# IN-16_Display.net
KiCad netlist of a schematic drawn in EAGLE
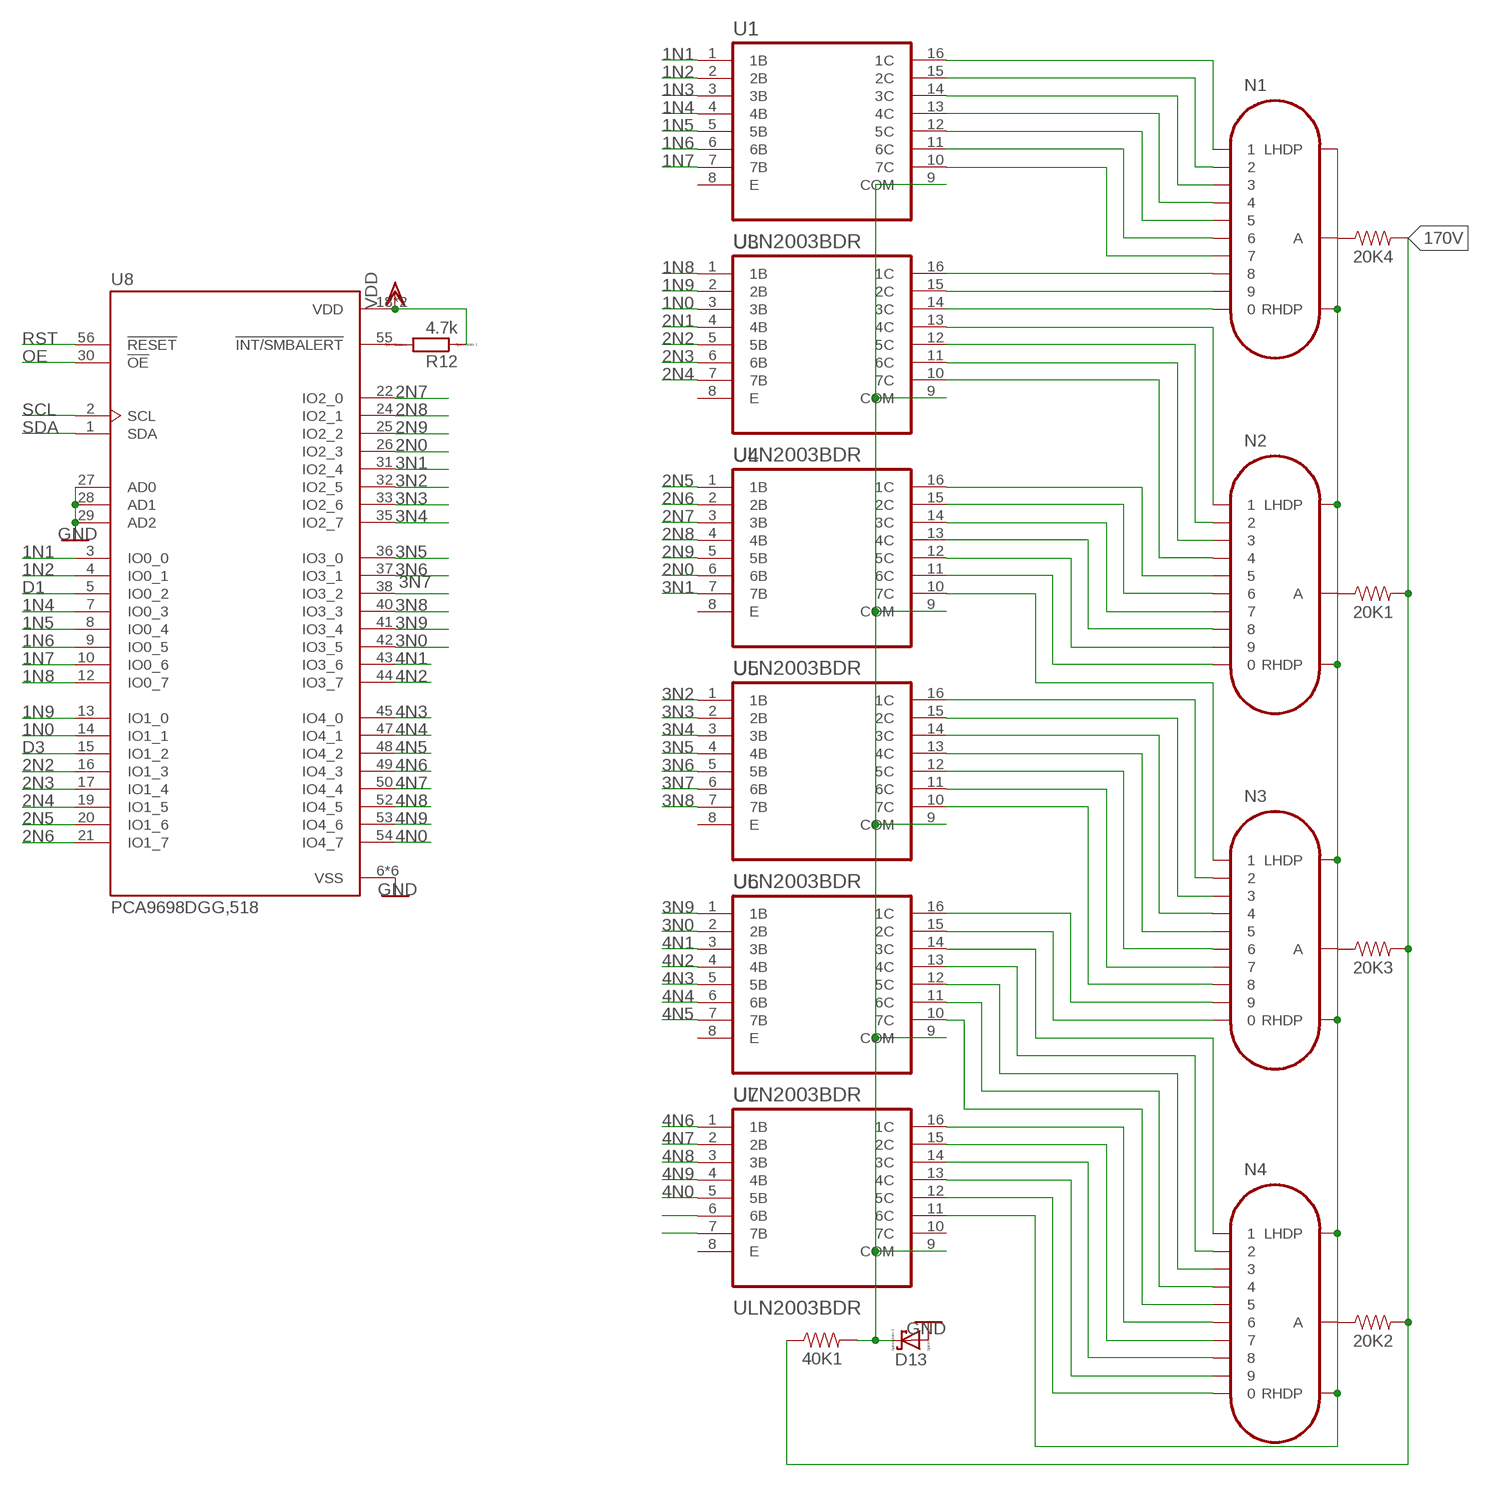
[diagram p0: schematic, sheet 1, part 1 of 2]
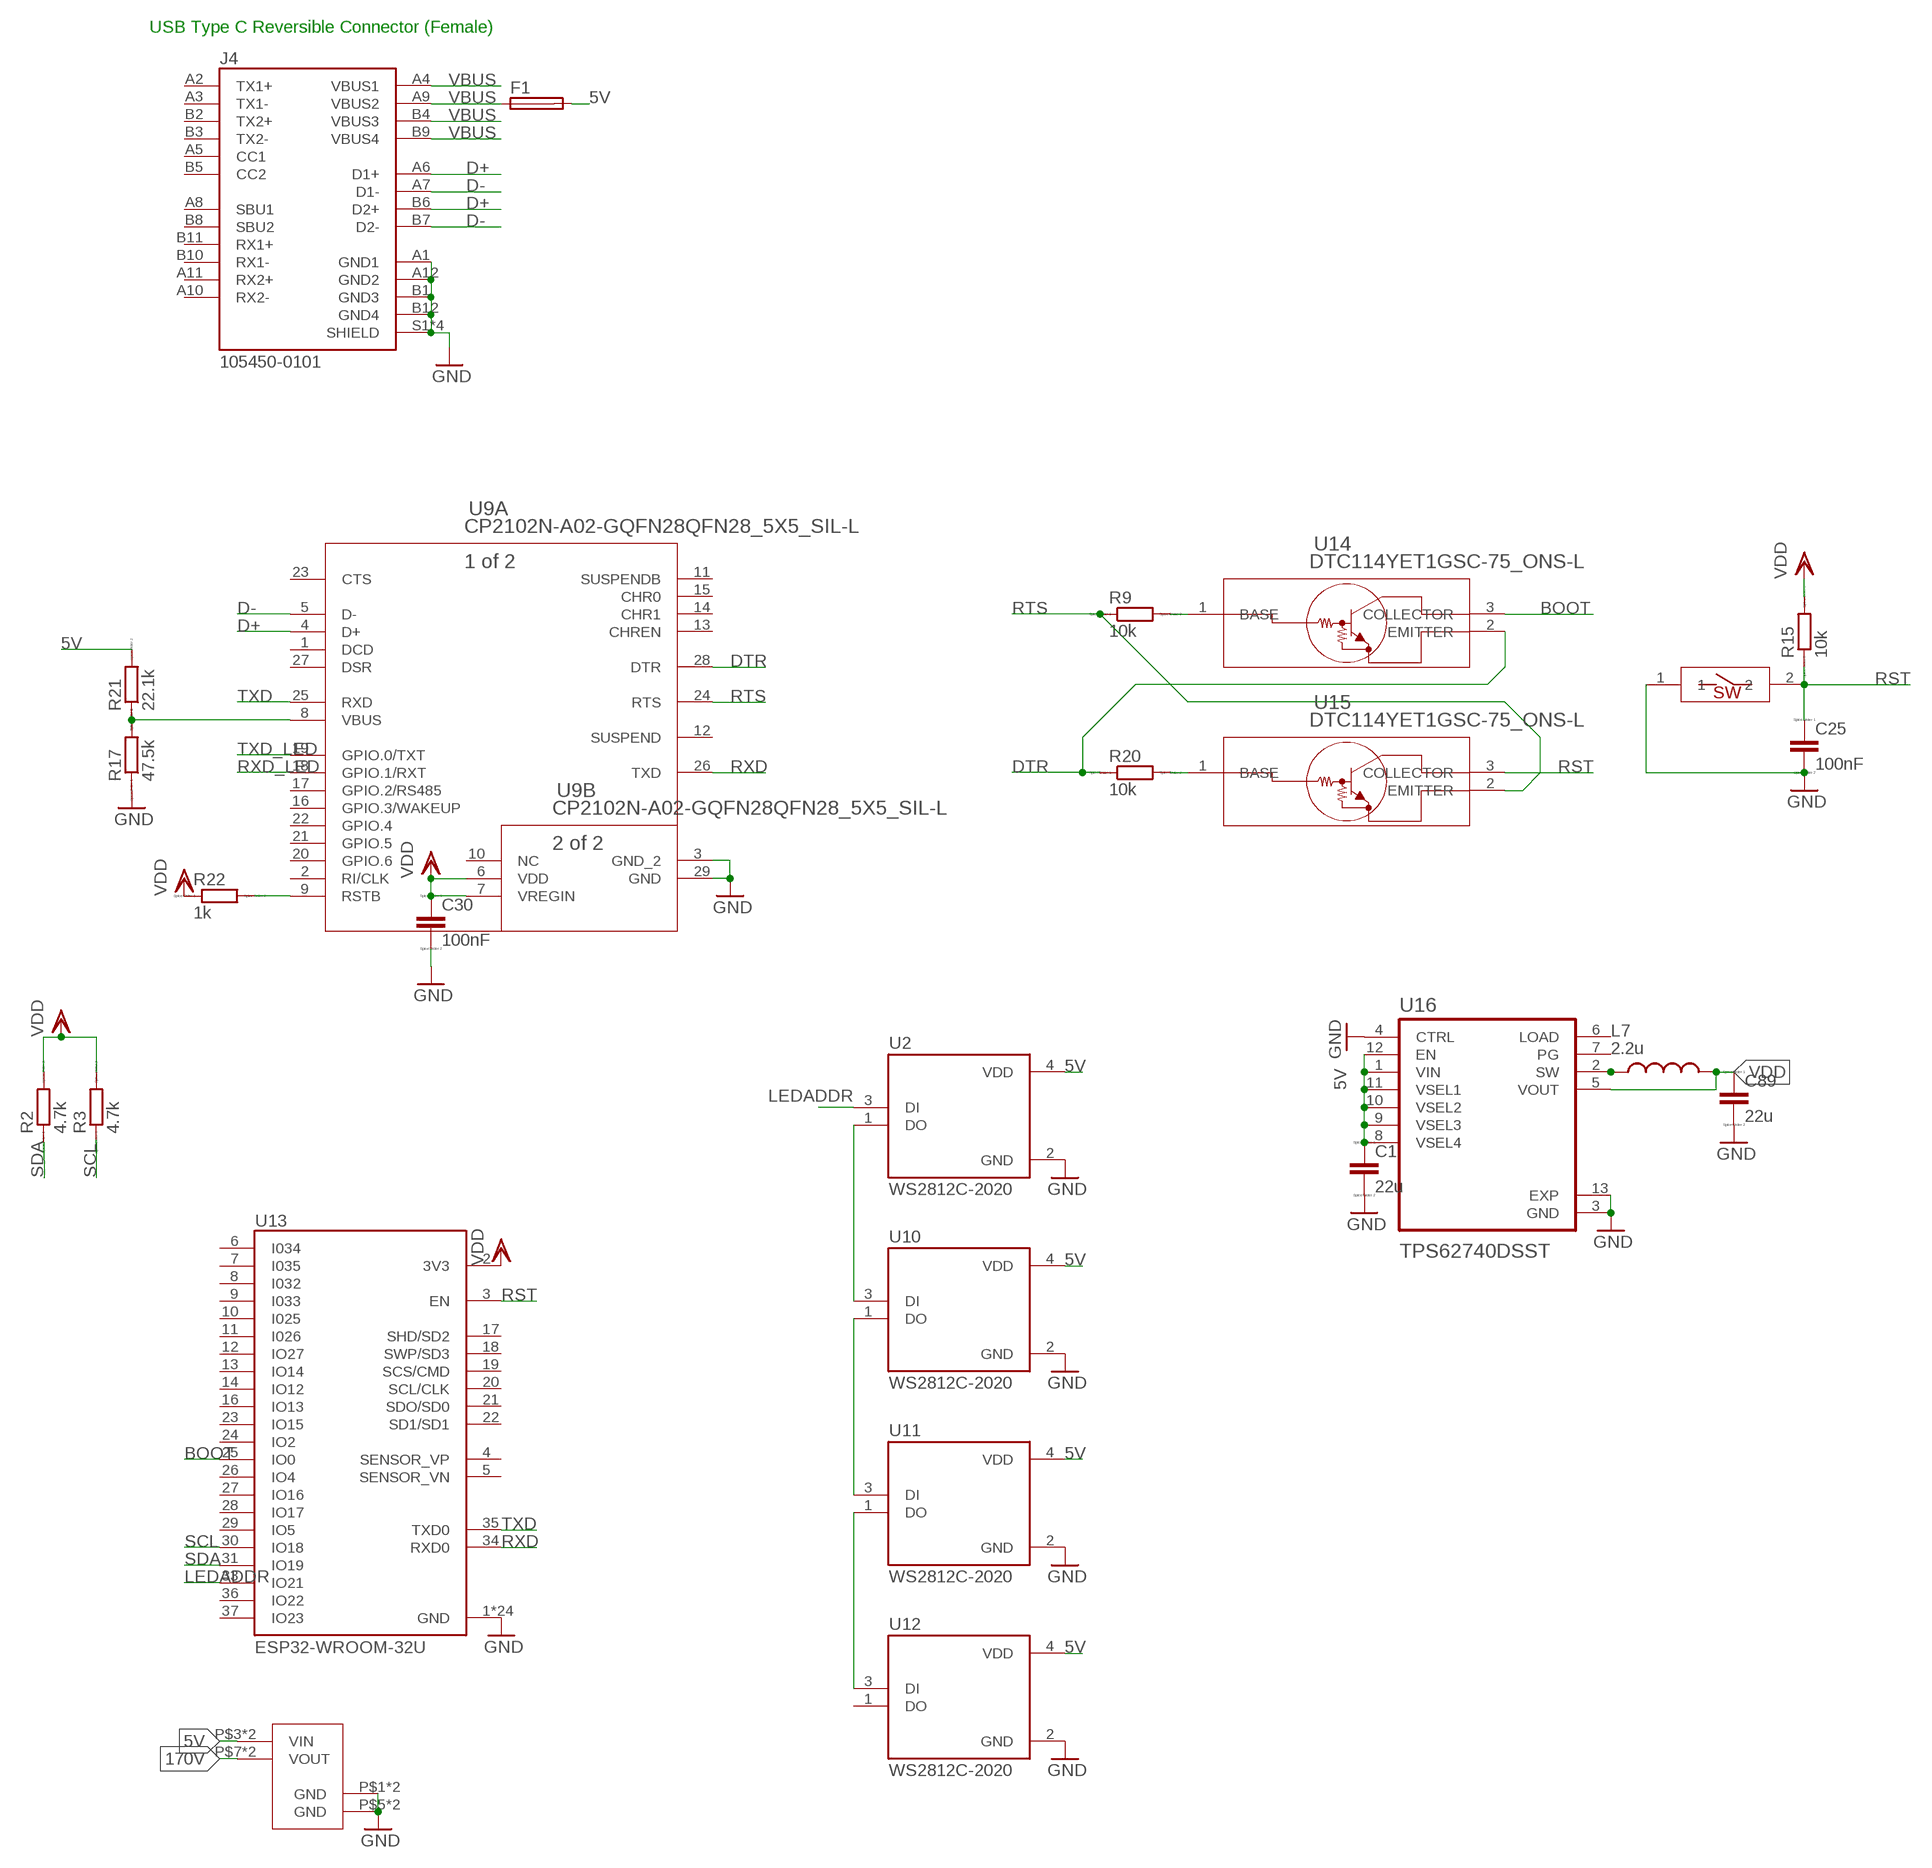
[diagram p1: schematic, sheet 1, part 2 of 2]

(export (version "E")
  (design (tool "Eeschema 10.0.6"))
  (components
    (comp (ref "20K1")
      (value "0.05")
      (footprint "eagle-import:1210")
      (libsource (lib "eagle-import") (part "0.1OHM-1210-1/2W-1%"))
    )
    (comp (ref "20K2")
      (value "0.05")
      (footprint "eagle-import:1210")
      (libsource (lib "eagle-import") (part "0.1OHM-1210-1/2W-1%"))
    )
    (comp (ref "20K3")
      (value "0.05")
      (footprint "eagle-import:1210")
      (libsource (lib "eagle-import") (part "0.1OHM-1210-1/2W-1%"))
    )
    (comp (ref "20K4")
      (value "0.05")
      (footprint "eagle-import:1210")
      (libsource (lib "eagle-import") (part "0.1OHM-1210-1/2W-1%"))
    )
    (comp (ref "40K1")
      (value "0.05")
      (footprint "eagle-import:1210")
      (libsource (lib "eagle-import") (part "0.1OHM-1210-1/2W-1%"))
    )
    (comp (ref "C1")
      (value "22u")
      (footprint "eagle-import:C0603R")
      (libsource (lib "eagle-import") (part "CC0603R"))
    )
    (comp (ref "C25")
      (value "100nF")
      (footprint "eagle-import:C0402")
      (libsource (lib "eagle-import") (part "CC0402"))
    )
    (comp (ref "C30")
      (value "100nF")
      (footprint "eagle-import:C0402")
      (libsource (lib "eagle-import") (part "CC0402"))
    )
    (comp (ref "C89")
      (value "22u")
      (footprint "eagle-import:C0603R")
      (libsource (lib "eagle-import") (part "CC0603R"))
    )
    (comp (ref "D13")
      (value "SCHOTTKY-DIODE")
      (footprint "eagle-import:DIODE_SMB")
      (libsource (lib "eagle-import") (part "SCHOTTKY-DIODE"))
    )
    (comp (ref "F1")
      (value "MF-MSMF050-2")
      (footprint "eagle-import:1812")
      (fields
        (field (name "DIGIKEY_PART_NUMBER") "MF-MSMF050-2TR-ND")
        (field (name "MANUFACTURER") "Bourns Inc.")
        (field (name "CREATED_BY") "PCBLayout.com")
      )
      (libsource (lib "eagle-import") (part "MF-MSMF050-2"))
    )
    (comp (ref "J4")
      (value "105450-0101")
      (footprint "eagle-import:MOLEX_105450-0101")
      (fields (field (name "MF") "Molex") (field (name "MP") "1054500101"))
      (libsource (lib "eagle-import") (part "105450-0101"))
    )
    (comp (ref "L7")
      (value "2.2u")
      (footprint "eagle-import:INDC3225X120N")
      (fields (field (name "MF") "Murata") (field (name "MP") "1277AS-H-1R5M=P2"))
      (libsource (lib "eagle-import") (part "1277AS-H-1R5M=P2"))
    )
    (comp (ref "N1")
      (value "IN-16")
      (footprint "eagle-import:IN-16")
      (libsource (lib "eagle-import") (part "IN-16"))
    )
    (comp (ref "N2")
      (value "IN-16")
      (footprint "eagle-import:IN-16")
      (libsource (lib "eagle-import") (part "IN-16"))
    )
    (comp (ref "N3")
      (value "IN-16")
      (footprint "eagle-import:IN-16")
      (libsource (lib "eagle-import") (part "IN-16"))
    )
    (comp (ref "N4")
      (value "IN-16")
      (footprint "eagle-import:IN-16")
      (libsource (lib "eagle-import") (part "IN-16"))
    )
    (comp (ref "R2")
      (value "4.7k")
      (footprint "eagle-import:R0402")
      (libsource (lib "eagle-import") (part "RR0402"))
    )
    (comp (ref "R3")
      (value "4.7k")
      (footprint "eagle-import:R0402")
      (libsource (lib "eagle-import") (part "RR0402"))
    )
    (comp (ref "R9")
      (value "10k")
      (footprint "eagle-import:R0402")
      (libsource (lib "eagle-import") (part "RR0402"))
    )
    (comp (ref "R12")
      (value "4.7k")
      (footprint "eagle-import:R0402")
      (libsource (lib "eagle-import") (part "RR0402"))
    )
    (comp (ref "R15")
      (value "10k")
      (footprint "eagle-import:R0402")
      (libsource (lib "eagle-import") (part "RR0402"))
    )
    (comp (ref "R17")
      (value "47.5k")
      (footprint "eagle-import:R0402")
      (libsource (lib "eagle-import") (part "RR0402"))
    )
    (comp (ref "R20")
      (value "10k")
      (footprint "eagle-import:R0402")
      (libsource (lib "eagle-import") (part "RR0402"))
    )
    (comp (ref "R21")
      (value "22.1k")
      (footprint "eagle-import:R0402")
      (libsource (lib "eagle-import") (part "RR0402"))
    )
    (comp (ref "R22")
      (value "1k")
      (footprint "eagle-import:R0402")
      (libsource (lib "eagle-import") (part "RR0402"))
    )
    (comp (ref "RESET")
      (value "SMDSWITCH")
      (footprint "eagle-import:RESC4217X170")
      (libsource (lib "eagle-import") (part "SMDSWITCH"))
    )
    (comp (ref "U$1")
      (value "HVPSU")
      (footprint "eagle-import:HVPSU")
      (libsource (lib "eagle-import") (part "HVPSU"))
    )
    (comp (ref "U1")
      (value "ULN2003BDR")
      (footprint "eagle-import:SOIC127P600X175-16N")
      (fields (field (name "MF") "Texas Instruments"))
      (libsource (lib "eagle-import") (part "ULN2003BDR"))
    )
    (comp (ref "U2")
      (value "WS2812C-2020")
      (footprint "eagle-import:LED_WS2812C-2020")
      (fields (field (name "MF") "Worldsemi"))
      (libsource (lib "eagle-import") (part "WS2812C-2020"))
    )
    (comp (ref "U3")
      (value "ULN2003BDR")
      (footprint "eagle-import:SOIC127P600X175-16N")
      (fields (field (name "MF") "Texas Instruments"))
      (libsource (lib "eagle-import") (part "ULN2003BDR"))
    )
    (comp (ref "U4")
      (value "ULN2003BDR")
      (footprint "eagle-import:SOIC127P600X175-16N")
      (fields (field (name "MF") "Texas Instruments"))
      (libsource (lib "eagle-import") (part "ULN2003BDR"))
    )
    (comp (ref "U5")
      (value "ULN2003BDR")
      (footprint "eagle-import:SOIC127P600X175-16N")
      (fields (field (name "MF") "Texas Instruments"))
      (libsource (lib "eagle-import") (part "ULN2003BDR"))
    )
    (comp (ref "U6")
      (value "ULN2003BDR")
      (footprint "eagle-import:SOIC127P600X175-16N")
      (fields (field (name "MF") "Texas Instruments"))
      (libsource (lib "eagle-import") (part "ULN2003BDR"))
    )
    (comp (ref "U7")
      (value "ULN2003BDR")
      (footprint "eagle-import:SOIC127P600X175-16N")
      (fields (field (name "MF") "Texas Instruments"))
      (libsource (lib "eagle-import") (part "ULN2003BDR"))
    )
    (comp (ref "U8")
      (value "PCA9698DGG,518")
      (footprint "eagle-import:SOP50P810X120-56N")
      (fields (field (name "MF") "NXP USA"))
      (libsource (lib "eagle-import") (part "PCA9698DGG,518"))
    )
    (comp (ref "U9")
      (value "CP2102N-A02-GQFN28QFN28_5X5_SIL-L")
      (footprint "eagle-import:QFN28_5X5_SIL-L")
      (fields
        (field (name "MANUFACTURER_PART_NUMBER") "CP2102N-A02-GQFN28")
        (field (name "COPYRIGHT") "Copyright (C) 2018 Accelerated Designs. All rights reserved")
      )
      (libsource (lib "eagle-import") (part "CP2102N-A02-GQFN28QFN28_5X5_SIL-L"))
    )
    (comp (ref "U10")
      (value "WS2812C-2020")
      (footprint "eagle-import:LED_WS2812C-2020")
      (fields (field (name "MF") "Worldsemi"))
      (libsource (lib "eagle-import") (part "WS2812C-2020"))
    )
    (comp (ref "U11")
      (value "WS2812C-2020")
      (footprint "eagle-import:LED_WS2812C-2020")
      (fields (field (name "MF") "Worldsemi"))
      (libsource (lib "eagle-import") (part "WS2812C-2020"))
    )
    (comp (ref "U12")
      (value "WS2812C-2020")
      (footprint "eagle-import:LED_WS2812C-2020")
      (fields (field (name "MF") "Worldsemi"))
      (libsource (lib "eagle-import") (part "WS2812C-2020"))
    )
    (comp (ref "U13")
      (value "ESP32-WROOM-32U")
      (footprint "eagle-import:XCVR_ESP32-WROOM-32U")
      (fields (field (name "MF") "Espressif Systems"))
      (libsource (lib "eagle-import") (part "ESP32-WROOM-32U"))
    )
    (comp (ref "U14")
      (value "DTC114YET1GSC-75_ONS-L")
      (footprint "eagle-import:SC-75_ONS-L")
      (fields
        (field (name "MANUFACTURER_PART_NUMBER") "DTC114YET1G")
        (field (name "COPYRIGHT") "Copyright (C) 2018 Accelerated Designs. All rights reserved")
      )
      (libsource (lib "eagle-import") (part "DTC114YET1GSC-75_ONS-L"))
    )
    (comp (ref "U15")
      (value "DTC114YET1GSC-75_ONS-L")
      (footprint "eagle-import:SC-75_ONS-L")
      (fields
        (field (name "MANUFACTURER_PART_NUMBER") "DTC114YET1G")
        (field (name "COPYRIGHT") "Copyright (C) 2018 Accelerated Designs. All rights reserved")
      )
      (libsource (lib "eagle-import") (part "DTC114YET1GSC-75_ONS-L"))
    )
    (comp (ref "U16")
      (value "TPS62740DSST")
      (footprint "eagle-import:VREG_LM27762DSSR")
      (fields (field (name "MF") "Texas Instruments") (field (name "MP") "TPS62740DSS"))
      (libsource (lib "eagle-import") (part "TPS62740DSST"))
    )
  )
  (nets
    (net (code "1") (name "/1N0") (class "Default")
      (node (ref "U3") (pin "3") (pinfunction "3B_3") (pintype "input"))
      (node (ref "U8") (pin "14") (pinfunction "IO1_1_14") (pintype "bidirectional"))
    )
    (net (code "2") (name "/1N1") (class "Default")
      (node (ref "U1") (pin "1") (pinfunction "1B_1") (pintype "input"))
      (node (ref "U8") (pin "3") (pinfunction "IO0_0_3") (pintype "bidirectional"))
    )
    (net (code "3") (name "/1N2") (class "Default")
      (node (ref "U1") (pin "2") (pinfunction "2B_2") (pintype "input"))
      (node (ref "U8") (pin "4") (pinfunction "IO0_1_4") (pintype "bidirectional"))
    )
    (net (code "4") (name "/1N3") (class "Default")
      (node (ref "U1") (pin "3") (pinfunction "3B_3") (pintype "input"))
    )
    (net (code "5") (name "/1N4") (class "Default")
      (node (ref "U1") (pin "4") (pinfunction "4B_4") (pintype "input"))
      (node (ref "U8") (pin "7") (pinfunction "IO0_3_7") (pintype "bidirectional"))
    )
    (net (code "6") (name "/1N5") (class "Default")
      (node (ref "U1") (pin "5") (pinfunction "5B_5") (pintype "input"))
      (node (ref "U8") (pin "8") (pinfunction "IO0_4_8") (pintype "bidirectional"))
    )
    (net (code "7") (name "/1N6") (class "Default")
      (node (ref "U1") (pin "6") (pinfunction "6B_6") (pintype "input"))
      (node (ref "U8") (pin "9") (pinfunction "IO0_5_9") (pintype "bidirectional"))
    )
    (net (code "8") (name "/1N7") (class "Default")
      (node (ref "U1") (pin "7") (pinfunction "7B_7") (pintype "input"))
      (node (ref "U8") (pin "10") (pinfunction "IO0_6_10") (pintype "bidirectional"))
    )
    (net (code "9") (name "/1N8") (class "Default")
      (node (ref "U3") (pin "1") (pinfunction "1B_1") (pintype "input"))
      (node (ref "U8") (pin "12") (pinfunction "IO0_7_12") (pintype "bidirectional"))
    )
    (net (code "10") (name "/1N9") (class "Default")
      (node (ref "U3") (pin "2") (pinfunction "2B_2") (pintype "input"))
      (node (ref "U8") (pin "13") (pinfunction "IO1_0_13") (pintype "bidirectional"))
    )
    (net (code "11") (name "/2N0") (class "Default")
      (node (ref "U4") (pin "6") (pinfunction "6B_6") (pintype "input"))
      (node (ref "U8") (pin "26") (pinfunction "IO2_3_26") (pintype "bidirectional"))
    )
    (net (code "12") (name "/2N1") (class "Default")
      (node (ref "U3") (pin "4") (pinfunction "4B_4") (pintype "input"))
    )
    (net (code "13") (name "/2N2") (class "Default")
      (node (ref "U3") (pin "5") (pinfunction "5B_5") (pintype "input"))
      (node (ref "U8") (pin "16") (pinfunction "IO1_3_16") (pintype "bidirectional"))
    )
    (net (code "14") (name "/2N3") (class "Default")
      (node (ref "U3") (pin "6") (pinfunction "6B_6") (pintype "input"))
      (node (ref "U8") (pin "17") (pinfunction "IO1_4_17") (pintype "bidirectional"))
    )
    (net (code "15") (name "/2N4") (class "Default")
      (node (ref "U3") (pin "7") (pinfunction "7B_7") (pintype "input"))
      (node (ref "U8") (pin "19") (pinfunction "IO1_5_19") (pintype "bidirectional"))
    )
    (net (code "16") (name "/2N5") (class "Default")
      (node (ref "U4") (pin "1") (pinfunction "1B_1") (pintype "input"))
      (node (ref "U8") (pin "20") (pinfunction "IO1_6_20") (pintype "bidirectional"))
    )
    (net (code "17") (name "/2N6") (class "Default")
      (node (ref "U4") (pin "2") (pinfunction "2B_2") (pintype "input"))
      (node (ref "U8") (pin "21") (pinfunction "IO1_7_21") (pintype "bidirectional"))
    )
    (net (code "18") (name "/2N7") (class "Default")
      (node (ref "U4") (pin "3") (pinfunction "3B_3") (pintype "input"))
      (node (ref "U8") (pin "22") (pinfunction "IO2_0_22") (pintype "bidirectional"))
    )
    (net (code "19") (name "/2N8") (class "Default")
      (node (ref "U4") (pin "4") (pinfunction "4B_4") (pintype "input"))
      (node (ref "U8") (pin "24") (pinfunction "IO2_1_24") (pintype "bidirectional"))
    )
    (net (code "20") (name "/2N9") (class "Default")
      (node (ref "U4") (pin "5") (pinfunction "5B_5") (pintype "input"))
      (node (ref "U8") (pin "25") (pinfunction "IO2_2_25") (pintype "bidirectional"))
    )
    (net (code "21") (name "/3N0") (class "Default")
      (node (ref "U6") (pin "2") (pinfunction "2B_2") (pintype "input"))
      (node (ref "U8") (pin "42") (pinfunction "IO3_5_42") (pintype "bidirectional"))
    )
    (net (code "22") (name "/3N1") (class "Default")
      (node (ref "U4") (pin "7") (pinfunction "7B_7") (pintype "input"))
      (node (ref "U8") (pin "31") (pinfunction "IO2_4_31") (pintype "bidirectional"))
    )
    (net (code "23") (name "/3N2") (class "Default")
      (node (ref "U5") (pin "1") (pinfunction "1B_1") (pintype "input"))
      (node (ref "U8") (pin "32") (pinfunction "IO2_5_32") (pintype "bidirectional"))
    )
    (net (code "24") (name "/3N3") (class "Default")
      (node (ref "U5") (pin "2") (pinfunction "2B_2") (pintype "input"))
      (node (ref "U8") (pin "33") (pinfunction "IO2_6_33") (pintype "bidirectional"))
    )
    (net (code "25") (name "/3N4") (class "Default")
      (node (ref "U5") (pin "3") (pinfunction "3B_3") (pintype "input"))
      (node (ref "U8") (pin "35") (pinfunction "IO2_7_35") (pintype "bidirectional"))
    )
    (net (code "26") (name "/3N5") (class "Default")
      (node (ref "U5") (pin "4") (pinfunction "4B_4") (pintype "input"))
      (node (ref "U8") (pin "36") (pinfunction "IO3_0_36") (pintype "bidirectional"))
    )
    (net (code "27") (name "/3N6") (class "Default")
      (node (ref "U5") (pin "5") (pinfunction "5B_5") (pintype "input"))
      (node (ref "U8") (pin "37") (pinfunction "IO3_1_37") (pintype "bidirectional"))
    )
    (net (code "28") (name "/3N7") (class "Default")
      (node (ref "U5") (pin "6") (pinfunction "6B_6") (pintype "input"))
      (node (ref "U8") (pin "38") (pinfunction "IO3_2_38") (pintype "bidirectional"))
    )
    (net (code "29") (name "/3N8") (class "Default")
      (node (ref "U5") (pin "7") (pinfunction "7B_7") (pintype "input"))
      (node (ref "U8") (pin "40") (pinfunction "IO3_3_40") (pintype "bidirectional"))
    )
    (net (code "30") (name "/3N9") (class "Default")
      (node (ref "U6") (pin "1") (pinfunction "1B_1") (pintype "input"))
      (node (ref "U8") (pin "41") (pinfunction "IO3_4_41") (pintype "bidirectional"))
    )
    (net (code "31") (name "/4N0") (class "Default")
      (node (ref "U7") (pin "5") (pinfunction "5B_5") (pintype "input"))
      (node (ref "U8") (pin "54") (pinfunction "IO4_7_54") (pintype "bidirectional"))
    )
    (net (code "32") (name "/4N1") (class "Default")
      (node (ref "U6") (pin "3") (pinfunction "3B_3") (pintype "input"))
      (node (ref "U8") (pin "43") (pinfunction "IO3_6_43") (pintype "bidirectional"))
    )
    (net (code "33") (name "/4N2") (class "Default")
      (node (ref "U6") (pin "4") (pinfunction "4B_4") (pintype "input"))
      (node (ref "U8") (pin "44") (pinfunction "IO3_7_44") (pintype "bidirectional"))
    )
    (net (code "34") (name "/4N3") (class "Default")
      (node (ref "U6") (pin "5") (pinfunction "5B_5") (pintype "input"))
      (node (ref "U8") (pin "45") (pinfunction "IO4_0_45") (pintype "bidirectional"))
    )
    (net (code "35") (name "/4N4") (class "Default")
      (node (ref "U6") (pin "6") (pinfunction "6B_6") (pintype "input"))
      (node (ref "U8") (pin "47") (pinfunction "IO4_1_47") (pintype "bidirectional"))
    )
    (net (code "36") (name "/4N5") (class "Default")
      (node (ref "U6") (pin "7") (pinfunction "7B_7") (pintype "input"))
      (node (ref "U8") (pin "48") (pinfunction "IO4_2_48") (pintype "bidirectional"))
    )
    (net (code "37") (name "/4N6") (class "Default")
      (node (ref "U7") (pin "1") (pinfunction "1B_1") (pintype "input"))
      (node (ref "U8") (pin "49") (pinfunction "IO4_3_49") (pintype "bidirectional"))
    )
    (net (code "38") (name "/4N7") (class "Default")
      (node (ref "U7") (pin "2") (pinfunction "2B_2") (pintype "input"))
      (node (ref "U8") (pin "50") (pinfunction "IO4_4_50") (pintype "bidirectional"))
    )
    (net (code "39") (name "/4N8") (class "Default")
      (node (ref "U7") (pin "3") (pinfunction "3B_3") (pintype "input"))
      (node (ref "U8") (pin "52") (pinfunction "IO4_5_52") (pintype "bidirectional"))
    )
    (net (code "40") (name "/4N9") (class "Default")
      (node (ref "U7") (pin "4") (pinfunction "4B_4") (pintype "input"))
      (node (ref "U8") (pin "53") (pinfunction "IO4_6_53") (pintype "bidirectional"))
    )
    (net (code "41") (name "/BOOT") (class "Default")
      (node (ref "U13") (pin "25") (pinfunction "IO0_25") (pintype "bidirectional"))
      (node (ref "U14") (pin "3") (pinfunction "COLLECTOR_3") (pintype "output"))
    )
    (net (code "42") (name "/D+") (class "Default")
      (node (ref "J4") (pin "A6") (pinfunction "D1+_A6") (pintype "passive"))
      (node (ref "J4") (pin "B6") (pinfunction "D2+_B6") (pintype "passive"))
      (node (ref "U9") (pin "4") (pinfunction "D+_4") (pintype "input"))
    )
    (net (code "43") (name "/D-") (class "Default")
      (node (ref "J4") (pin "A7") (pinfunction "D1-_A7") (pintype "passive"))
      (node (ref "J4") (pin "B7") (pinfunction "D2-_B7") (pintype "passive"))
      (node (ref "U9") (pin "5") (pinfunction "D-_5") (pintype "input"))
    )
    (net (code "44") (name "/D1") (class "Default")
      (node (ref "U8") (pin "5") (pinfunction "IO0_2_5") (pintype "bidirectional"))
    )
    (net (code "45") (name "/D3") (class "Default")
      (node (ref "U8") (pin "15") (pinfunction "IO1_2_15") (pintype "bidirectional"))
    )
    (net (code "46") (name "/DTR") (class "Default")
      (node (ref "R20") (pin "1") (pinfunction "1_1") (pintype "passive"))
      (node (ref "U14") (pin "2") (pinfunction "EMITTER_2") (pintype "passive"))
      (node (ref "U9") (pin "28") (pinfunction "DTR_28") (pintype "output"))
    )
    (net (code "47") (name "/LEDADDR") (class "Default")
      (node (ref "U13") (pin "33") (pinfunction "IO21_33") (pintype "bidirectional"))
      (node (ref "U2") (pin "3") (pinfunction "DI_3") (pintype "input"))
    )
    (net (code "48") (name "/OE") (class "Default")
      (node (ref "U8") (pin "30") (pinfunction "~{OE}_30") (pintype "input"))
    )
    (net (code "49") (name "/RST") (class "Default")
      (node (ref "C25") (pin "1") (pinfunction "1_1") (pintype "passive"))
      (node (ref "R15") (pin "1") (pinfunction "1_1") (pintype "passive"))
      (node (ref "RESET") (pin "2") (pinfunction "2_2") (pintype "bidirectional"))
      (node (ref "U13") (pin "3") (pinfunction "EN_3") (pintype "input"))
      (node (ref "U15") (pin "3") (pinfunction "COLLECTOR_3") (pintype "output"))
      (node (ref "U8") (pin "56") (pinfunction "~{RESET}_56") (pintype "input"))
    )
    (net (code "50") (name "/RTS") (class "Default")
      (node (ref "R9") (pin "1") (pinfunction "1_1") (pintype "passive"))
      (node (ref "U15") (pin "2") (pinfunction "EMITTER_2") (pintype "passive"))
      (node (ref "U9") (pin "24") (pinfunction "RTS_24") (pintype "output"))
    )
    (net (code "51") (name "/RXD") (class "Default")
      (node (ref "U13") (pin "34") (pinfunction "RXD0_34") (pintype "bidirectional"))
      (node (ref "U9") (pin "26") (pinfunction "TXD_26") (pintype "output"))
    )
    (net (code "52") (name "/RXD_LED") (class "Default")
      (node (ref "U9") (pin "18") (pinfunction "GPIO.1/RXT_18") (pintype "bidirectional"))
    )
    (net (code "53") (name "/SCL") (class "Default")
      (node (ref "R3") (pin "1") (pinfunction "1_1") (pintype "passive"))
      (node (ref "U13") (pin "30") (pinfunction "IO18_30") (pintype "bidirectional"))
      (node (ref "U8") (pin "2") (pinfunction "SCL_2") (pintype "input"))
    )
    (net (code "54") (name "/SDA") (class "Default")
      (node (ref "R2") (pin "1") (pinfunction "1_1") (pintype "passive"))
      (node (ref "U13") (pin "31") (pinfunction "IO19_31") (pintype "bidirectional"))
      (node (ref "U8") (pin "1") (pinfunction "SDA_1") (pintype "bidirectional"))
    )
    (net (code "55") (name "/TXD") (class "Default")
      (node (ref "U13") (pin "35") (pinfunction "TXD0_35") (pintype "bidirectional"))
      (node (ref "U9") (pin "25") (pinfunction "RXD_25") (pintype "input"))
    )
    (net (code "56") (name "/TXD_LED") (class "Default")
      (node (ref "U9") (pin "19") (pinfunction "GPIO.0/TXT_19") (pintype "bidirectional"))
    )
    (net (code "57") (name "/VBUS") (class "Default")
      (node (ref "F1") (pin "1") (pinfunction "1_1") (pintype "passive"))
      (node (ref "J4") (pin "A4") (pinfunction "VBUS1_A4") (pintype "passive"))
      (node (ref "J4") (pin "A9") (pinfunction "VBUS2_A9") (pintype "passive"))
      (node (ref "J4") (pin "B4") (pinfunction "VBUS3_B4") (pintype "passive"))
      (node (ref "J4") (pin "B9") (pinfunction "VBUS4_B9") (pintype "passive"))
    )
    (net (code "58") (name "5V") (class "Default")
      (node (ref "C1") (pin "1") (pinfunction "1_1") (pintype "passive"))
      (node (ref "F1") (pin "2") (pinfunction "2_2") (pintype "passive"))
      (node (ref "R21") (pin "2") (pinfunction "2_2") (pintype "passive"))
      (node (ref "U$1") (pin "P$3") (pinfunction "VIN_P$3") (pintype "bidirectional"))
      (node (ref "U$1") (pin "P$4") (pinfunction "VIN_P$4") (pintype "bidirectional"))
      (node (ref "U10") (pin "4") (pinfunction "VDD_4") (pintype "power_in"))
      (node (ref "U11") (pin "4") (pinfunction "VDD_4") (pintype "power_in"))
      (node (ref "U12") (pin "4") (pinfunction "VDD_4") (pintype "power_in"))
      (node (ref "U16") (pin "1") (pinfunction "VIN_1") (pintype "input"))
      (node (ref "U16") (pin "10") (pinfunction "VSEL2_10") (pintype "input"))
      (node (ref "U16") (pin "11") (pinfunction "VSEL1_11") (pintype "input"))
      (node (ref "U16") (pin "12") (pinfunction "EN_12") (pintype "input"))
      (node (ref "U16") (pin "8") (pinfunction "VSEL4_8") (pintype "input"))
      (node (ref "U16") (pin "9") (pinfunction "VSEL3_9") (pintype "input"))
      (node (ref "U2") (pin "4") (pinfunction "VDD_4") (pintype "power_in"))
    )
    (net (code "59") (name "170V") (class "Default")
      (node (ref "20K1") (pin "2") (pinfunction "2_2") (pintype "passive"))
      (node (ref "20K2") (pin "2") (pinfunction "2_2") (pintype "passive"))
      (node (ref "20K3") (pin "2") (pinfunction "2_2") (pintype "passive"))
      (node (ref "20K4") (pin "2") (pinfunction "2_2") (pintype "passive"))
      (node (ref "40K1") (pin "1") (pinfunction "1_1") (pintype "passive"))
      (node (ref "U$1") (pin "P$7") (pinfunction "VOUT_P$7") (pintype "bidirectional"))
      (node (ref "U$1") (pin "P$8") (pinfunction "VOUT_P$8") (pintype "bidirectional"))
    )
    (net (code "60") (name "GND") (class "Default")
      (node (ref "C1") (pin "2") (pinfunction "2_2") (pintype "passive"))
      (node (ref "C25") (pin "2") (pinfunction "2_2") (pintype "passive"))
      (node (ref "C30") (pin "2") (pinfunction "2_2") (pintype "passive"))
      (node (ref "C89") (pin "2") (pinfunction "2_2") (pintype "passive"))
      (node (ref "D13") (pin "A") (pinfunction "C_A") (pintype "passive"))
      (node (ref "J4") (pin "A1") (pinfunction "GND1_A1") (pintype "passive"))
      (node (ref "J4") (pin "A12") (pinfunction "GND2_A12") (pintype "passive"))
      (node (ref "J4") (pin "B1") (pinfunction "GND3_B1") (pintype "passive"))
      (node (ref "J4") (pin "B12") (pinfunction "GND4_B12") (pintype "passive"))
      (node (ref "J4") (pin "S1") (pinfunction "SHIELD_S1") (pintype "passive"))
      (node (ref "J4") (pin "S2") (pinfunction "SHIELD_S2") (pintype "passive"))
      (node (ref "J4") (pin "S3") (pinfunction "SHIELD_S3") (pintype "passive"))
      (node (ref "J4") (pin "S4") (pinfunction "SHIELD_S4") (pintype "passive"))
      (node (ref "R17") (pin "1") (pinfunction "1_1") (pintype "passive"))
      (node (ref "RESET") (pin "1") (pinfunction "1_1") (pintype "bidirectional"))
      (node (ref "U$1") (pin "P$1") (pinfunction "GND_P$1") (pintype "bidirectional"))
      (node (ref "U$1") (pin "P$2") (pinfunction "GND_P$2") (pintype "bidirectional"))
      (node (ref "U$1") (pin "P$5") (pinfunction "GND_P$5") (pintype "bidirectional"))
      (node (ref "U$1") (pin "P$6") (pinfunction "GND_P$6") (pintype "bidirectional"))
      (node (ref "U10") (pin "2") (pinfunction "GND_2") (pintype "power_in"))
      (node (ref "U11") (pin "2") (pinfunction "GND_2") (pintype "power_in"))
      (node (ref "U12") (pin "2") (pinfunction "GND_2") (pintype "power_in"))
      (node (ref "U13") (pin "1") (pinfunction "GND_1") (pintype "power_in"))
      (node (ref "U13") (pin "15") (pinfunction "GND_15") (pintype "power_in"))
      (node (ref "U13") (pin "38") (pinfunction "GND_38") (pintype "power_in"))
      (node (ref "U13") (pin "G.1") (pinfunction "GND_G.1") (pintype "power_in"))
      (node (ref "U13") (pin "G.10") (pinfunction "GND_G.10") (pintype "power_in"))
      (node (ref "U13") (pin "G.11") (pinfunction "GND_G.11") (pintype "power_in"))
      (node (ref "U13") (pin "G.12") (pinfunction "GND_G.12") (pintype "power_in"))
      (node (ref "U13") (pin "G.13") (pinfunction "GND_G.13") (pintype "power_in"))
      (node (ref "U13") (pin "G.14") (pinfunction "GND_G.14") (pintype "power_in"))
      (node (ref "U13") (pin "G.15") (pinfunction "GND_G.15") (pintype "power_in"))
      (node (ref "U13") (pin "G.16") (pinfunction "GND_G.16") (pintype "power_in"))
      (node (ref "U13") (pin "G.17") (pinfunction "GND_G.17") (pintype "power_in"))
      (node (ref "U13") (pin "G.18") (pinfunction "GND_G.18") (pintype "power_in"))
      (node (ref "U13") (pin "G.19") (pinfunction "GND_G.19") (pintype "power_in"))
      (node (ref "U13") (pin "G.2") (pinfunction "GND_G.2") (pintype "power_in"))
      (node (ref "U13") (pin "G.20") (pinfunction "GND_G.20") (pintype "power_in"))
      (node (ref "U13") (pin "G.21") (pinfunction "GND_G.21") (pintype "power_in"))
      (node (ref "U13") (pin "G.22") (pinfunction "GND_G.22") (pintype "power_in"))
      (node (ref "U13") (pin "G.4") (pinfunction "GND_G.4") (pintype "power_in"))
      (node (ref "U13") (pin "G.5") (pinfunction "GND_G.5") (pintype "power_in"))
      (node (ref "U13") (pin "G.6") (pinfunction "GND_G.6") (pintype "power_in"))
      (node (ref "U13") (pin "G.7") (pinfunction "GND_G.7") (pintype "power_in"))
      (node (ref "U13") (pin "G.8") (pinfunction "GND_G.8") (pintype "power_in"))
      (node (ref "U13") (pin "G.9") (pinfunction "GND_G.9") (pintype "power_in"))
      (node (ref "U16") (pin "13") (pinfunction "EXP_13") (pintype "power_in"))
      (node (ref "U16") (pin "3") (pinfunction "GND_3") (pintype "power_in"))
      (node (ref "U16") (pin "4") (pinfunction "CTRL_4") (pintype "input"))
      (node (ref "U2") (pin "2") (pinfunction "GND_2") (pintype "power_in"))
      (node (ref "U8") (pin "11") (pinfunction "VSS_11") (pintype "power_in"))
      (node (ref "U8") (pin "23") (pinfunction "VSS_23") (pintype "power_in"))
      (node (ref "U8") (pin "27") (pinfunction "AD0_27") (pintype "input"))
      (node (ref "U8") (pin "28") (pinfunction "AD1_28") (pintype "input"))
      (node (ref "U8") (pin "29") (pinfunction "AD2_29") (pintype "input"))
      (node (ref "U8") (pin "34") (pinfunction "VSS_34") (pintype "power_in"))
      (node (ref "U8") (pin "39") (pinfunction "VSS_39") (pintype "power_in"))
      (node (ref "U8") (pin "51") (pinfunction "VSS_51") (pintype "power_in"))
      (node (ref "U8") (pin "6") (pinfunction "VSS_6") (pintype "power_in"))
      (node (ref "U9") (pin "29") (pinfunction "GND_29") (pintype "passive"))
      (node (ref "U9") (pin "3") (pinfunction "GND_2_3") (pintype "passive"))
    )
    (net (code "61") (name "Net-(20K1-Pad1)") (class "Default")
      (node (ref "20K1") (pin "1") (pinfunction "1_1") (pintype "passive"))
      (node (ref "N2") (pin "A") (pinfunction "A_A") (pintype "bidirectional"))
    )
    (net (code "62") (name "Net-(20K2-Pad1)") (class "Default")
      (node (ref "20K2") (pin "1") (pinfunction "1_1") (pintype "passive"))
      (node (ref "N4") (pin "A") (pinfunction "A_A") (pintype "bidirectional"))
    )
    (net (code "63") (name "Net-(20K3-Pad1)") (class "Default")
      (node (ref "20K3") (pin "1") (pinfunction "1_1") (pintype "passive"))
      (node (ref "N3") (pin "A") (pinfunction "A_A") (pintype "bidirectional"))
    )
    (net (code "64") (name "Net-(20K4-Pad1)") (class "Default")
      (node (ref "20K4") (pin "1") (pinfunction "1_1") (pintype "passive"))
      (node (ref "N1") (pin "A") (pinfunction "A_A") (pintype "bidirectional"))
    )
    (net (code "65") (name "Net-(D13-A)") (class "Default")
      (node (ref "40K1") (pin "2") (pinfunction "2_2") (pintype "passive"))
      (node (ref "D13") (pin "C") (pinfunction "A_C") (pintype "passive"))
      (node (ref "U1") (pin "9") (pinfunction "COM_9") (pintype "output"))
      (node (ref "U3") (pin "9") (pinfunction "COM_9") (pintype "output"))
      (node (ref "U4") (pin "9") (pinfunction "COM_9") (pintype "output"))
      (node (ref "U5") (pin "9") (pinfunction "COM_9") (pintype "output"))
      (node (ref "U6") (pin "9") (pinfunction "COM_9") (pintype "output"))
      (node (ref "U7") (pin "9") (pinfunction "COM_9") (pintype "output"))
    )
    (net (code "66") (name "Net-(U1-1C)") (class "Default")
      (node (ref "N1") (pin "1") (pinfunction "1_1") (pintype "bidirectional"))
      (node (ref "U1") (pin "16") (pinfunction "1C_16") (pintype "output"))
    )
    (net (code "67") (name "Net-(U1-2C)") (class "Default")
      (node (ref "N1") (pin "2") (pinfunction "2_2") (pintype "bidirectional"))
      (node (ref "U1") (pin "15") (pinfunction "2C_15") (pintype "output"))
    )
    (net (code "68") (name "Net-(U1-3C)") (class "Default")
      (node (ref "N1") (pin "3") (pinfunction "3_3") (pintype "bidirectional"))
      (node (ref "U1") (pin "14") (pinfunction "3C_14") (pintype "output"))
    )
    (net (code "69") (name "Net-(U1-4C)") (class "Default")
      (node (ref "N1") (pin "4") (pinfunction "4_4") (pintype "bidirectional"))
      (node (ref "U1") (pin "13") (pinfunction "4C_13") (pintype "output"))
    )
    (net (code "70") (name "Net-(U1-5C)") (class "Default")
      (node (ref "N1") (pin "5") (pinfunction "5_5") (pintype "bidirectional"))
      (node (ref "U1") (pin "12") (pinfunction "5C_12") (pintype "output"))
    )
    (net (code "71") (name "Net-(U1-6C)") (class "Default")
      (node (ref "N1") (pin "6") (pinfunction "6_6") (pintype "bidirectional"))
      (node (ref "U1") (pin "11") (pinfunction "6C_11") (pintype "output"))
    )
    (net (code "72") (name "Net-(U1-7C)") (class "Default")
      (node (ref "N1") (pin "7") (pinfunction "7_7") (pintype "bidirectional"))
      (node (ref "U1") (pin "10") (pinfunction "7C_10") (pintype "output"))
    )
    (net (code "73") (name "Net-(U3-1C)") (class "Default")
      (node (ref "N1") (pin "8") (pinfunction "8_8") (pintype "bidirectional"))
      (node (ref "U3") (pin "16") (pinfunction "1C_16") (pintype "output"))
    )
    (net (code "74") (name "Net-(U3-2C)") (class "Default")
      (node (ref "N1") (pin "9") (pinfunction "9_9") (pintype "bidirectional"))
      (node (ref "U3") (pin "15") (pinfunction "2C_15") (pintype "output"))
    )
    (net (code "75") (name "Net-(U3-3C)") (class "Default")
      (node (ref "N1") (pin "0") (pinfunction "0_0") (pintype "bidirectional"))
      (node (ref "U3") (pin "14") (pinfunction "3C_14") (pintype "output"))
    )
    (net (code "76") (name "Net-(U3-4C)") (class "Default")
      (node (ref "N2") (pin "1") (pinfunction "1_1") (pintype "bidirectional"))
      (node (ref "U3") (pin "13") (pinfunction "4C_13") (pintype "output"))
    )
    (net (code "77") (name "Net-(U3-5C)") (class "Default")
      (node (ref "N2") (pin "2") (pinfunction "2_2") (pintype "bidirectional"))
      (node (ref "U3") (pin "12") (pinfunction "5C_12") (pintype "output"))
    )
    (net (code "78") (name "Net-(U3-6C)") (class "Default")
      (node (ref "N2") (pin "3") (pinfunction "3_3") (pintype "bidirectional"))
      (node (ref "U3") (pin "11") (pinfunction "6C_11") (pintype "output"))
    )
    (net (code "79") (name "Net-(U3-7C)") (class "Default")
      (node (ref "N2") (pin "4") (pinfunction "4_4") (pintype "bidirectional"))
      (node (ref "U3") (pin "10") (pinfunction "7C_10") (pintype "output"))
    )
    (net (code "80") (name "Net-(U4-1C)") (class "Default")
      (node (ref "N2") (pin "5") (pinfunction "5_5") (pintype "bidirectional"))
      (node (ref "U4") (pin "16") (pinfunction "1C_16") (pintype "output"))
    )
    (net (code "81") (name "Net-(U4-2C)") (class "Default")
      (node (ref "N2") (pin "6") (pinfunction "6_6") (pintype "bidirectional"))
      (node (ref "U4") (pin "15") (pinfunction "2C_15") (pintype "output"))
    )
    (net (code "82") (name "Net-(U4-3C)") (class "Default")
      (node (ref "N2") (pin "7") (pinfunction "7_7") (pintype "bidirectional"))
      (node (ref "U4") (pin "14") (pinfunction "3C_14") (pintype "output"))
    )
    (net (code "83") (name "Net-(U4-4C)") (class "Default")
      (node (ref "N2") (pin "8") (pinfunction "8_8") (pintype "bidirectional"))
      (node (ref "U4") (pin "13") (pinfunction "4C_13") (pintype "output"))
    )
    (net (code "84") (name "Net-(U4-5C)") (class "Default")
      (node (ref "N2") (pin "9") (pinfunction "9_9") (pintype "bidirectional"))
      (node (ref "U4") (pin "12") (pinfunction "5C_12") (pintype "output"))
    )
    (net (code "85") (name "Net-(U4-6C)") (class "Default")
      (node (ref "N2") (pin "0") (pinfunction "0_0") (pintype "bidirectional"))
      (node (ref "U4") (pin "11") (pinfunction "6C_11") (pintype "output"))
    )
    (net (code "86") (name "Net-(U4-7C)") (class "Default")
      (node (ref "N3") (pin "1") (pinfunction "1_1") (pintype "bidirectional"))
      (node (ref "U4") (pin "10") (pinfunction "7C_10") (pintype "output"))
    )
    (net (code "87") (name "Net-(U5-1C)") (class "Default")
      (node (ref "N3") (pin "2") (pinfunction "2_2") (pintype "bidirectional"))
      (node (ref "U5") (pin "16") (pinfunction "1C_16") (pintype "output"))
    )
    (net (code "88") (name "Net-(U5-2C)") (class "Default")
      (node (ref "N3") (pin "3") (pinfunction "3_3") (pintype "bidirectional"))
      (node (ref "U5") (pin "15") (pinfunction "2C_15") (pintype "output"))
    )
    (net (code "89") (name "Net-(U5-3C)") (class "Default")
      (node (ref "N3") (pin "4") (pinfunction "4_4") (pintype "bidirectional"))
      (node (ref "U5") (pin "14") (pinfunction "3C_14") (pintype "output"))
    )
    (net (code "90") (name "Net-(U5-4C)") (class "Default")
      (node (ref "N3") (pin "5") (pinfunction "5_5") (pintype "bidirectional"))
      (node (ref "U5") (pin "13") (pinfunction "4C_13") (pintype "output"))
    )
    (net (code "91") (name "Net-(U5-5C)") (class "Default")
      (node (ref "N3") (pin "6") (pinfunction "6_6") (pintype "bidirectional"))
      (node (ref "U5") (pin "12") (pinfunction "5C_12") (pintype "output"))
    )
    (net (code "92") (name "Net-(U5-6C)") (class "Default")
      (node (ref "N3") (pin "7") (pinfunction "7_7") (pintype "bidirectional"))
      (node (ref "U5") (pin "11") (pinfunction "6C_11") (pintype "output"))
    )
    (net (code "93") (name "Net-(U5-7C)") (class "Default")
      (node (ref "N3") (pin "8") (pinfunction "8_8") (pintype "bidirectional"))
      (node (ref "U5") (pin "10") (pinfunction "7C_10") (pintype "output"))
    )
    (net (code "94") (name "Net-(U6-1C)") (class "Default")
      (node (ref "N3") (pin "9") (pinfunction "9_9") (pintype "bidirectional"))
      (node (ref "U6") (pin "16") (pinfunction "1C_16") (pintype "output"))
    )
    (net (code "95") (name "Net-(U6-2C)") (class "Default")
      (node (ref "N3") (pin "0") (pinfunction "0_0") (pintype "bidirectional"))
      (node (ref "U6") (pin "15") (pinfunction "2C_15") (pintype "output"))
    )
    (net (code "96") (name "Net-(U6-3C)") (class "Default")
      (node (ref "N4") (pin "1") (pinfunction "1_1") (pintype "bidirectional"))
      (node (ref "U6") (pin "14") (pinfunction "3C_14") (pintype "output"))
    )
    (net (code "97") (name "Net-(U6-4C)") (class "Default")
      (node (ref "N4") (pin "2") (pinfunction "2_2") (pintype "bidirectional"))
      (node (ref "U6") (pin "13") (pinfunction "4C_13") (pintype "output"))
    )
    (net (code "98") (name "Net-(U6-5C)") (class "Default")
      (node (ref "N4") (pin "3") (pinfunction "3_3") (pintype "bidirectional"))
      (node (ref "U6") (pin "12") (pinfunction "5C_12") (pintype "output"))
    )
    (net (code "99") (name "Net-(U6-6C)") (class "Default")
      (node (ref "N4") (pin "4") (pinfunction "4_4") (pintype "bidirectional"))
      (node (ref "U6") (pin "11") (pinfunction "6C_11") (pintype "output"))
    )
    (net (code "100") (name "Net-(U6-7C)") (class "Default")
      (node (ref "N4") (pin "5") (pinfunction "5_5") (pintype "bidirectional"))
      (node (ref "U6") (pin "10") (pinfunction "7C_10") (pintype "output"))
    )
    (net (code "101") (name "Net-(U7-1C)") (class "Default")
      (node (ref "N4") (pin "6") (pinfunction "6_6") (pintype "bidirectional"))
      (node (ref "U7") (pin "16") (pinfunction "1C_16") (pintype "output"))
    )
    (net (code "102") (name "Net-(U7-2C)") (class "Default")
      (node (ref "N4") (pin "7") (pinfunction "7_7") (pintype "bidirectional"))
      (node (ref "U7") (pin "15") (pinfunction "2C_15") (pintype "output"))
    )
    (net (code "103") (name "Net-(U7-3C)") (class "Default")
      (node (ref "N4") (pin "8") (pinfunction "8_8") (pintype "bidirectional"))
      (node (ref "U7") (pin "14") (pinfunction "3C_14") (pintype "output"))
    )
    (net (code "104") (name "Net-(U7-4C)") (class "Default")
      (node (ref "N4") (pin "9") (pinfunction "9_9") (pintype "bidirectional"))
      (node (ref "U7") (pin "13") (pinfunction "4C_13") (pintype "output"))
    )
    (net (code "105") (name "Net-(U7-5C)") (class "Default")
      (node (ref "N4") (pin "0") (pinfunction "0_0") (pintype "bidirectional"))
      (node (ref "U7") (pin "12") (pinfunction "5C_12") (pintype "output"))
    )
    (net (code "106") (name "Net-(U7-6C)") (class "Default")
      (node (ref "N1") (pin "LHDP") (pinfunction "LHDP_LHDP") (pintype "bidirectional"))
      (node (ref "N1") (pin "RHDP") (pinfunction "RHDP_RHDP") (pintype "bidirectional"))
      (node (ref "N2") (pin "LHDP") (pinfunction "LHDP_LHDP") (pintype "bidirectional"))
      (node (ref "N2") (pin "RHDP") (pinfunction "RHDP_RHDP") (pintype "bidirectional"))
      (node (ref "N3") (pin "LHDP") (pinfunction "LHDP_LHDP") (pintype "bidirectional"))
      (node (ref "N3") (pin "RHDP") (pinfunction "RHDP_RHDP") (pintype "bidirectional"))
      (node (ref "N4") (pin "LHDP") (pinfunction "LHDP_LHDP") (pintype "bidirectional"))
      (node (ref "N4") (pin "RHDP") (pinfunction "RHDP_RHDP") (pintype "bidirectional"))
      (node (ref "U7") (pin "11") (pinfunction "6C_11") (pintype "output"))
    )
    (net (code "107") (name "Net-(U8-~{INT{slash}SMBALERT})") (class "Default")
      (node (ref "R12") (pin "2") (pinfunction "2_2") (pintype "passive"))
      (node (ref "U8") (pin "55") (pinfunction "~{INT/SMBALERT}_55") (pintype "output"))
    )
    (net (code "108") (name "Net-(U9A-RSTB)") (class "Default")
      (node (ref "R22") (pin "2") (pinfunction "2_2") (pintype "passive"))
      (node (ref "U9") (pin "9") (pinfunction "RSTB_9") (pintype "passive"))
    )
    (net (code "109") (name "Net-(U9A-VBUS)") (class "Default")
      (node (ref "R17") (pin "2") (pinfunction "2_2") (pintype "passive"))
      (node (ref "R21") (pin "1") (pinfunction "1_1") (pintype "passive"))
      (node (ref "U9") (pin "8") (pinfunction "VBUS_8") (pintype "input"))
    )
    (net (code "110") (name "Net-(U10-DI)") (class "Default")
      (node (ref "U10") (pin "3") (pinfunction "DI_3") (pintype "input"))
      (node (ref "U2") (pin "1") (pinfunction "DO_1") (pintype "output"))
    )
    (net (code "111") (name "Net-(U10-DO)") (class "Default")
      (node (ref "U10") (pin "1") (pinfunction "DO_1") (pintype "output"))
      (node (ref "U11") (pin "3") (pinfunction "DI_3") (pintype "input"))
    )
    (net (code "112") (name "Net-(U11-DO)") (class "Default")
      (node (ref "U11") (pin "1") (pinfunction "DO_1") (pintype "output"))
      (node (ref "U12") (pin "3") (pinfunction "DI_3") (pintype "input"))
    )
    (net (code "113") (name "Net-(U14-BASE)") (class "Default")
      (node (ref "R9") (pin "2") (pinfunction "2_2") (pintype "passive"))
      (node (ref "U14") (pin "1") (pinfunction "BASE_1") (pintype "input"))
    )
    (net (code "114") (name "Net-(U15-BASE)") (class "Default")
      (node (ref "R20") (pin "2") (pinfunction "2_2") (pintype "passive"))
      (node (ref "U15") (pin "1") (pinfunction "BASE_1") (pintype "input"))
    )
    (net (code "115") (name "Net-(U16-SW)") (class "Default")
      (node (ref "L7") (pin "1") (pinfunction "1_1") (pintype "passive"))
      (node (ref "U16") (pin "2") (pinfunction "SW_2") (pintype "output"))
    )
    (net (code "116") (name "VDD") (class "Default")
      (node (ref "C30") (pin "1") (pinfunction "1_1") (pintype "passive"))
      (node (ref "C89") (pin "1") (pinfunction "1_1") (pintype "passive"))
      (node (ref "L7") (pin "2") (pinfunction "2_2") (pintype "passive"))
      (node (ref "R12") (pin "1") (pinfunction "1_1") (pintype "passive"))
      (node (ref "R15") (pin "2") (pinfunction "2_2") (pintype "passive"))
      (node (ref "R2") (pin "2") (pinfunction "2_2") (pintype "passive"))
      (node (ref "R22") (pin "1") (pinfunction "1_1") (pintype "passive"))
      (node (ref "R3") (pin "2") (pinfunction "2_2") (pintype "passive"))
      (node (ref "U13") (pin "2") (pinfunction "3V3_2") (pintype "power_in"))
      (node (ref "U16") (pin "5") (pinfunction "VOUT_5") (pintype "output"))
      (node (ref "U8") (pin "18") (pinfunction "VDD_18") (pintype "power_in"))
      (node (ref "U8") (pin "46") (pinfunction "VDD_46") (pintype "power_in"))
      (node (ref "U9") (pin "6") (pinfunction "VDD_6") (pintype "power_in"))
      (node (ref "U9") (pin "7") (pinfunction "VREGIN_7") (pintype "power_in"))
    )
    (net (code "117") (name "unconnected-(J4-CC1-PadA5)") (class "Default")
      (node (ref "J4") (pin "A5") (pinfunction "CC1_A5") (pintype "passive"))
    )
    (net (code "118") (name "unconnected-(J4-CC2-PadB5)") (class "Default")
      (node (ref "J4") (pin "B5") (pinfunction "CC2_B5") (pintype "passive"))
    )
    (net (code "119") (name "unconnected-(J4-RX1+-PadB11)") (class "Default")
      (node (ref "J4") (pin "B11") (pinfunction "RX1+_B11") (pintype "passive"))
    )
    (net (code "120") (name "unconnected-(J4-RX1--PadB10)") (class "Default")
      (node (ref "J4") (pin "B10") (pinfunction "RX1-_B10") (pintype "passive"))
    )
    (net (code "121") (name "unconnected-(J4-RX2+-PadA11)") (class "Default")
      (node (ref "J4") (pin "A11") (pinfunction "RX2+_A11") (pintype "passive"))
    )
    (net (code "122") (name "unconnected-(J4-RX2--PadA10)") (class "Default")
      (node (ref "J4") (pin "A10") (pinfunction "RX2-_A10") (pintype "passive"))
    )
    (net (code "123") (name "unconnected-(J4-SBU1-PadA8)") (class "Default")
      (node (ref "J4") (pin "A8") (pinfunction "SBU1_A8") (pintype "passive"))
    )
    (net (code "124") (name "unconnected-(J4-SBU2-PadB8)") (class "Default")
      (node (ref "J4") (pin "B8") (pinfunction "SBU2_B8") (pintype "passive"))
    )
    (net (code "125") (name "unconnected-(J4-TX1+-PadA2)") (class "Default")
      (node (ref "J4") (pin "A2") (pinfunction "TX1+_A2") (pintype "passive"))
    )
    (net (code "126") (name "unconnected-(J4-TX1--PadA3)") (class "Default")
      (node (ref "J4") (pin "A3") (pinfunction "TX1-_A3") (pintype "passive"))
    )
    (net (code "127") (name "unconnected-(J4-TX2+-PadB2)") (class "Default")
      (node (ref "J4") (pin "B2") (pinfunction "TX2+_B2") (pintype "passive"))
    )
    (net (code "128") (name "unconnected-(J4-TX2--PadB3)") (class "Default")
      (node (ref "J4") (pin "B3") (pinfunction "TX2-_B3") (pintype "passive"))
    )
    (net (code "129") (name "unconnected-(U1-E-Pad8)") (class "Default")
      (node (ref "U1") (pin "8") (pinfunction "E_8") (pintype "input"))
    )
    (net (code "130") (name "unconnected-(U3-E-Pad8)") (class "Default")
      (node (ref "U3") (pin "8") (pinfunction "E_8") (pintype "input"))
    )
    (net (code "131") (name "unconnected-(U4-E-Pad8)") (class "Default")
      (node (ref "U4") (pin "8") (pinfunction "E_8") (pintype "input"))
    )
    (net (code "132") (name "unconnected-(U5-E-Pad8)") (class "Default")
      (node (ref "U5") (pin "8") (pinfunction "E_8") (pintype "input"))
    )
    (net (code "133") (name "unconnected-(U6-E-Pad8)") (class "Default")
      (node (ref "U6") (pin "8") (pinfunction "E_8") (pintype "input"))
    )
    (net (code "134") (name "unconnected-(U7-6B-Pad6)") (class "Default")
      (node (ref "U7") (pin "6") (pinfunction "6B_6") (pintype "input"))
    )
    (net (code "135") (name "unconnected-(U7-7B-Pad7)") (class "Default")
      (node (ref "U7") (pin "7") (pinfunction "7B_7") (pintype "input"))
    )
    (net (code "136") (name "unconnected-(U7-7C-Pad10)") (class "Default")
      (node (ref "U7") (pin "10") (pinfunction "7C_10") (pintype "output"))
    )
    (net (code "137") (name "unconnected-(U7-E-Pad8)") (class "Default")
      (node (ref "U7") (pin "8") (pinfunction "E_8") (pintype "input"))
    )
    (net (code "138") (name "unconnected-(U9A-CHR0-Pad15)") (class "Default")
      (node (ref "U9") (pin "15") (pinfunction "CHR0_15") (pintype "output"))
    )
    (net (code "139") (name "unconnected-(U9A-CHR1-Pad14)") (class "Default")
      (node (ref "U9") (pin "14") (pinfunction "CHR1_14") (pintype "output"))
    )
    (net (code "140") (name "unconnected-(U9A-CHREN-Pad13)") (class "Default")
      (node (ref "U9") (pin "13") (pinfunction "CHREN_13") (pintype "output"))
    )
    (net (code "141") (name "unconnected-(U9A-CTS-Pad23)") (class "Default")
      (node (ref "U9") (pin "23") (pinfunction "CTS_23") (pintype "input"))
    )
    (net (code "142") (name "unconnected-(U9A-DCD-Pad1)") (class "Default")
      (node (ref "U9") (pin "1") (pinfunction "DCD_1") (pintype "input"))
    )
    (net (code "143") (name "unconnected-(U9A-DSR-Pad27)") (class "Default")
      (node (ref "U9") (pin "27") (pinfunction "DSR_27") (pintype "input"))
    )
    (net (code "144") (name "unconnected-(U9A-GPIO.2{slash}RS485-Pad17)") (class "Default")
      (node (ref "U9") (pin "17") (pinfunction "GPIO.2/RS485_17") (pintype "bidirectional"))
    )
    (net (code "145") (name "unconnected-(U9A-GPIO.3{slash}WAKEUP-Pad16)") (class "Default")
      (node (ref "U9") (pin "16") (pinfunction "GPIO.3/WAKEUP_16") (pintype "bidirectional"))
    )
    (net (code "146") (name "unconnected-(U9A-GPIO.4-Pad22)") (class "Default")
      (node (ref "U9") (pin "22") (pinfunction "GPIO.4_22") (pintype "bidirectional"))
    )
    (net (code "147") (name "unconnected-(U9A-GPIO.5-Pad21)") (class "Default")
      (node (ref "U9") (pin "21") (pinfunction "GPIO.5_21") (pintype "bidirectional"))
    )
    (net (code "148") (name "unconnected-(U9A-GPIO.6-Pad20)") (class "Default")
      (node (ref "U9") (pin "20") (pinfunction "GPIO.6_20") (pintype "bidirectional"))
    )
    (net (code "149") (name "unconnected-(U9A-RI{slash}CLK-Pad2)") (class "Default")
      (node (ref "U9") (pin "2") (pinfunction "RI/CLK_2") (pintype "bidirectional"))
    )
    (net (code "150") (name "unconnected-(U9A-SUSPEND-Pad12)") (class "Default")
      (node (ref "U9") (pin "12") (pinfunction "SUSPEND_12") (pintype "output"))
    )
    (net (code "151") (name "unconnected-(U9A-SUSPENDB-Pad11)") (class "Default")
      (node (ref "U9") (pin "11") (pinfunction "SUSPENDB_11") (pintype "output"))
    )
    (net (code "152") (name "unconnected-(U9B-NC-Pad10)") (class "Default")
      (node (ref "U9") (pin "10") (pinfunction "NC_10") (pintype "no_connect"))
    )
    (net (code "153") (name "unconnected-(U12-DO-Pad1)") (class "Default")
      (node (ref "U12") (pin "1") (pinfunction "DO_1") (pintype "output"))
    )
    (net (code "154") (name "unconnected-(U13-I025-Pad10)") (class "Default")
      (node (ref "U13") (pin "10") (pinfunction "I025_10") (pintype "bidirectional"))
    )
    (net (code "155") (name "unconnected-(U13-I026-Pad11)") (class "Default")
      (node (ref "U13") (pin "11") (pinfunction "I026_11") (pintype "bidirectional"))
    )
    (net (code "156") (name "unconnected-(U13-I032-Pad8)") (class "Default")
      (node (ref "U13") (pin "8") (pinfunction "I032_8") (pintype "bidirectional"))
    )
    (net (code "157") (name "unconnected-(U13-I033-Pad9)") (class "Default")
      (node (ref "U13") (pin "9") (pinfunction "I033_9") (pintype "bidirectional"))
    )
    (net (code "158") (name "unconnected-(U13-I034-Pad6)") (class "Default")
      (node (ref "U13") (pin "6") (pinfunction "I034_6") (pintype "input"))
    )
    (net (code "159") (name "unconnected-(U13-I035-Pad7)") (class "Default")
      (node (ref "U13") (pin "7") (pinfunction "I035_7") (pintype "input"))
    )
    (net (code "160") (name "unconnected-(U13-IO2-Pad24)") (class "Default")
      (node (ref "U13") (pin "24") (pinfunction "IO2_24") (pintype "bidirectional"))
    )
    (net (code "161") (name "unconnected-(U13-IO4-Pad26)") (class "Default")
      (node (ref "U13") (pin "26") (pinfunction "IO4_26") (pintype "bidirectional"))
    )
    (net (code "162") (name "unconnected-(U13-IO5-Pad29)") (class "Default")
      (node (ref "U13") (pin "29") (pinfunction "IO5_29") (pintype "bidirectional"))
    )
    (net (code "163") (name "unconnected-(U13-IO12-Pad14)") (class "Default")
      (node (ref "U13") (pin "14") (pinfunction "IO12_14") (pintype "bidirectional"))
    )
    (net (code "164") (name "unconnected-(U13-IO13-Pad16)") (class "Default")
      (node (ref "U13") (pin "16") (pinfunction "IO13_16") (pintype "bidirectional"))
    )
    (net (code "165") (name "unconnected-(U13-IO14-Pad13)") (class "Default")
      (node (ref "U13") (pin "13") (pinfunction "IO14_13") (pintype "bidirectional"))
    )
    (net (code "166") (name "unconnected-(U13-IO15-Pad23)") (class "Default")
      (node (ref "U13") (pin "23") (pinfunction "IO15_23") (pintype "bidirectional"))
    )
    (net (code "167") (name "unconnected-(U13-IO16-Pad27)") (class "Default")
      (node (ref "U13") (pin "27") (pinfunction "IO16_27") (pintype "bidirectional"))
    )
    (net (code "168") (name "unconnected-(U13-IO17-Pad28)") (class "Default")
      (node (ref "U13") (pin "28") (pinfunction "IO17_28") (pintype "bidirectional"))
    )
    (net (code "169") (name "unconnected-(U13-IO22-Pad36)") (class "Default")
      (node (ref "U13") (pin "36") (pinfunction "IO22_36") (pintype "bidirectional"))
    )
    (net (code "170") (name "unconnected-(U13-IO23-Pad37)") (class "Default")
      (node (ref "U13") (pin "37") (pinfunction "IO23_37") (pintype "bidirectional"))
    )
    (net (code "171") (name "unconnected-(U13-IO27-Pad12)") (class "Default")
      (node (ref "U13") (pin "12") (pinfunction "IO27_12") (pintype "bidirectional"))
    )
    (net (code "172") (name "unconnected-(U13-SCL{slash}CLK-Pad20)") (class "Default")
      (node (ref "U13") (pin "20") (pinfunction "SCL/CLK_20") (pintype "bidirectional"))
    )
    (net (code "173") (name "unconnected-(U13-SCS{slash}CMD-Pad19)") (class "Default")
      (node (ref "U13") (pin "19") (pinfunction "SCS/CMD_19") (pintype "bidirectional"))
    )
    (net (code "174") (name "unconnected-(U13-SD1{slash}SD1-Pad22)") (class "Default")
      (node (ref "U13") (pin "22") (pinfunction "SD1/SD1_22") (pintype "bidirectional"))
    )
    (net (code "175") (name "unconnected-(U13-SDO{slash}SD0-Pad21)") (class "Default")
      (node (ref "U13") (pin "21") (pinfunction "SDO/SD0_21") (pintype "bidirectional"))
    )
    (net (code "176") (name "unconnected-(U13-SENSOR_VN-Pad5)") (class "Default")
      (node (ref "U13") (pin "5") (pinfunction "SENSOR_VN_5") (pintype "input"))
    )
    (net (code "177") (name "unconnected-(U13-SENSOR_VP-Pad4)") (class "Default")
      (node (ref "U13") (pin "4") (pinfunction "SENSOR_VP_4") (pintype "input"))
    )
    (net (code "178") (name "unconnected-(U13-SHD{slash}SD2-Pad17)") (class "Default")
      (node (ref "U13") (pin "17") (pinfunction "SHD/SD2_17") (pintype "bidirectional"))
    )
    (net (code "179") (name "unconnected-(U13-SWP{slash}SD3-Pad18)") (class "Default")
      (node (ref "U13") (pin "18") (pinfunction "SWP/SD3_18") (pintype "bidirectional"))
    )
    (net (code "180") (name "unconnected-(U16-LOAD-Pad6)") (class "Default")
      (node (ref "U16") (pin "6") (pinfunction "LOAD_6") (pintype "output"))
    )
    (net (code "181") (name "unconnected-(U16-PG-Pad7)") (class "Default")
      (node (ref "U16") (pin "7") (pinfunction "PG_7") (pintype "output"))
    )
  )
)
